# Buzzer.net
KiCad netlist of a schematic drawn in Altium Designer
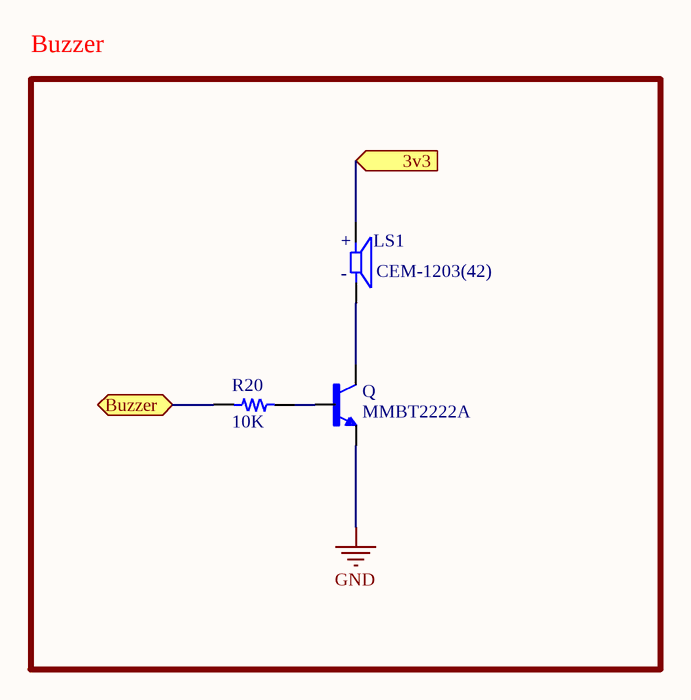
[diagram p0: Buzzer.SchDoc]

(export (version "E")
  (design (tool "Eeschema 10.0.6"))
  (components
    (comp (ref "LS1")
      (value "CEM-1203(42)")
      (footprint "CUI_CEM-1203(42)")
      (description "12 mm, 3.5 V, 85 dB, Through Hole, Magnetic Audio Transducer Buzzer")
      (fields (field (name "MF") "CUI Devices"))
      (libsource (lib "Buzzer 12mm") (part "CEM-1203(42)"))
    )
    (comp (ref "Q")
      (value "MMBT2222A")
      (footprint "SOT23")
      (description "Bipolar _BJT_ Transistor NPN 40V 600mA 270MHz 350mW Surface Mount SOT-23-3")
      (fields (field (name "MF") "STMicroelectronics"))
      (libsource (lib "MMBT2222A") (part "MMBT2222A"))
    )
    (comp (ref "R20")
      (value "10K")
      (footprint "RES 0805_2012")
      (description "SMT Resistor")
      (libsource (lib "Resistor") (part "Res 0805"))
    )
  )
  (nets
    (net (code "1") (name "/3v3") (class "Default")
      (node (ref "LS1") (pin "P") (pinfunction "P_P") (pintype "passive"))
    )
    (net (code "2") (name "/Buzzer") (class "Default")
      (node (ref "R20") (pin "1") (pinfunction "1_1") (pintype "passive"))
    )
    (net (code "3") (name "GND") (class "Default")
      (node (ref "Q") (pin "2") (pinfunction "E_2") (pintype "passive"))
    )
    (net (code "4") (name "Net-(Q-B)") (class "Default")
      (node (ref "Q") (pin "1") (pinfunction "B_1") (pintype "passive"))
      (node (ref "R20") (pin "2") (pinfunction "2_2") (pintype "passive"))
    )
    (net (code "5") (name "Net-(Q-C)") (class "Default")
      (node (ref "LS1") (pin "N") (pinfunction "N_N") (pintype "passive"))
      (node (ref "Q") (pin "3") (pinfunction "C_3") (pintype "passive"))
    )
  )
)
